# GD32F470.net
KiCad netlist of a schematic drawn in EAGLE
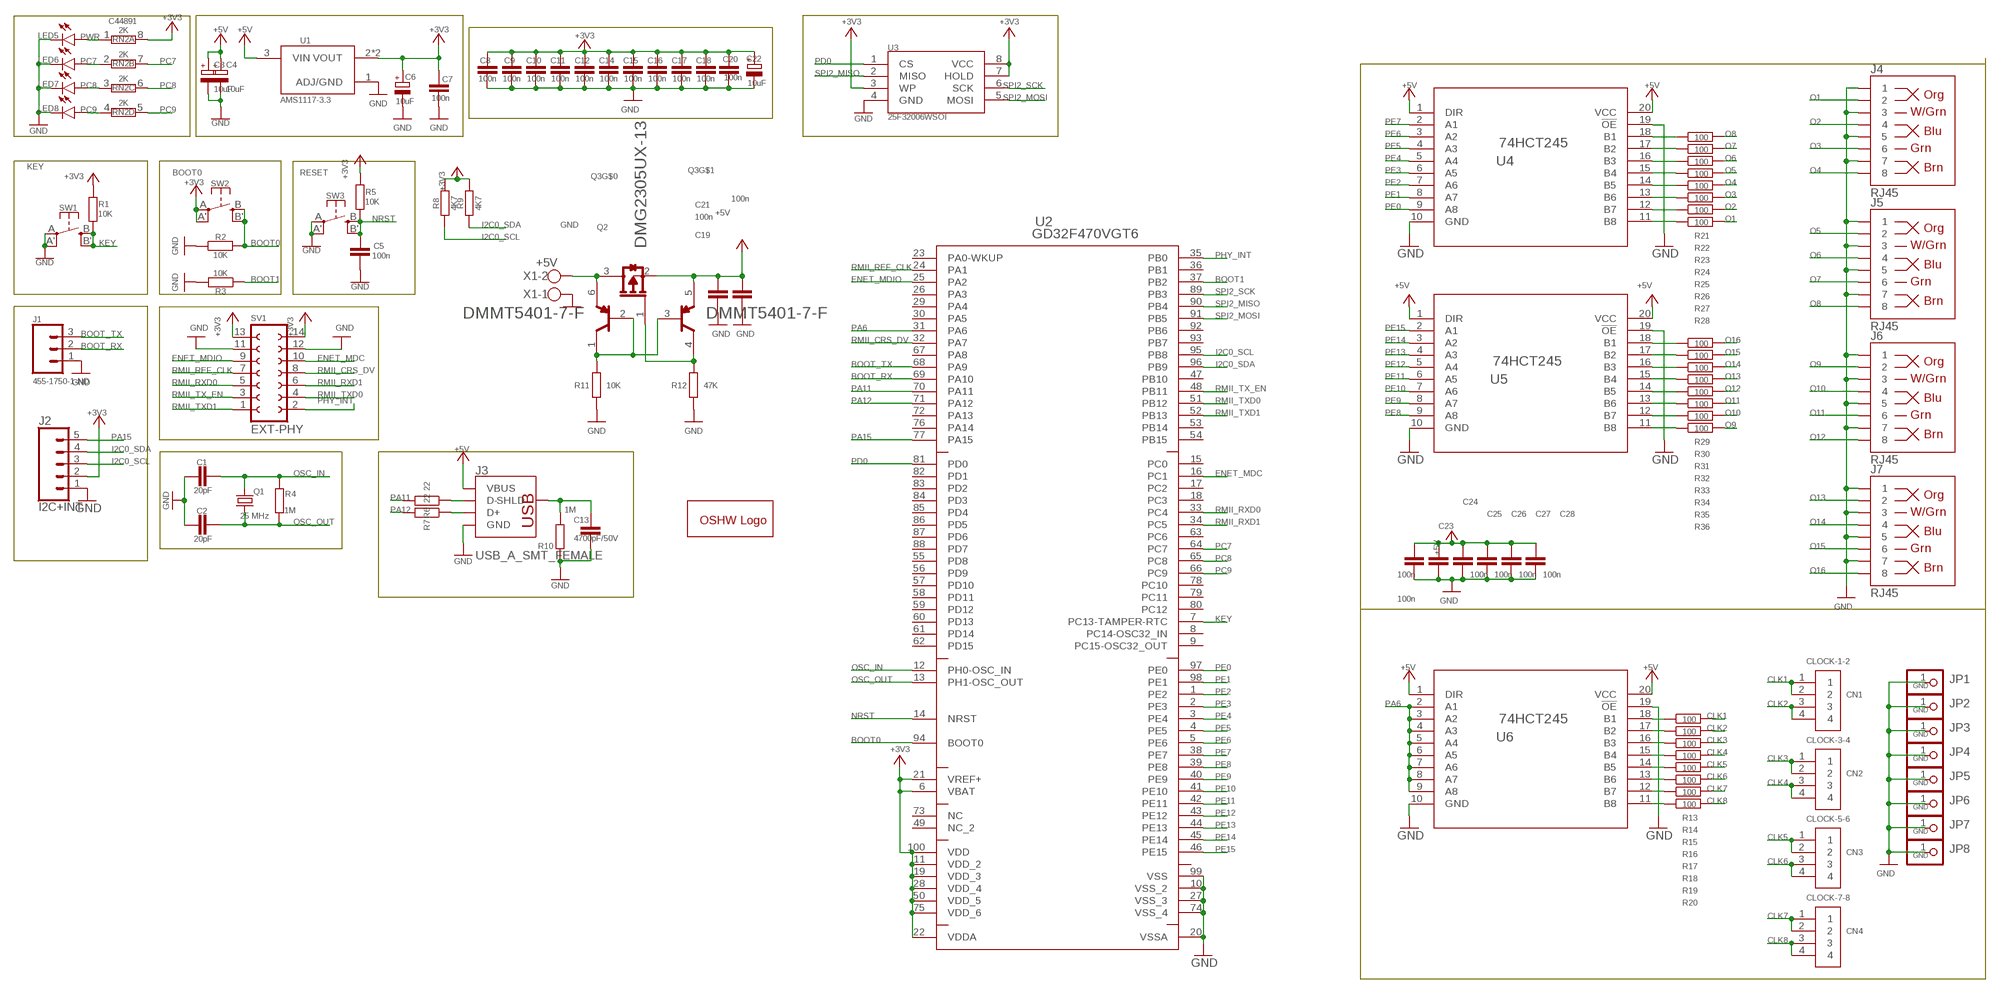
[diagram p0: schematic, sheet 1]

(export (version "E")
  (design (tool "Eeschema 10.0.6"))
  (components
    (comp (ref "C1")
      (value "20pF")
      (footprint "eagle-import:C0603")
      (libsource (lib "eagle-import") (part "C-EUC0603"))
    )
    (comp (ref "C2")
      (value "20pF")
      (footprint "eagle-import:C0603")
      (libsource (lib "eagle-import") (part "C-EUC0603"))
    )
    (comp (ref "C3")
      (value "10uF")
      (footprint "eagle-import:A_3216-18R")
      (libsource (lib "eagle-import") (part "CPOL-EUA/3216-18R"))
    )
    (comp (ref "C4")
      (value "10uF")
      (footprint "eagle-import:A_3216-18R")
      (libsource (lib "eagle-import") (part "CPOL-EUA/3216-18R"))
    )
    (comp (ref "C5")
      (value "100n")
      (footprint "eagle-import:C0603")
      (libsource (lib "eagle-import") (part "C-EUC0603"))
    )
    (comp (ref "C6")
      (value "10uF")
      (footprint "eagle-import:A_3216-18R")
      (libsource (lib "eagle-import") (part "CPOL-EUA/3216-18R"))
    )
    (comp (ref "C7")
      (value "100n")
      (footprint "eagle-import:C0603")
      (libsource (lib "eagle-import") (part "C-EUC0603"))
    )
    (comp (ref "C8")
      (value "100n")
      (footprint "eagle-import:C0603")
      (libsource (lib "eagle-import") (part "C-EUC0603"))
    )
    (comp (ref "C9")
      (value "100n")
      (footprint "eagle-import:C0603")
      (libsource (lib "eagle-import") (part "C-EUC0603"))
    )
    (comp (ref "C10")
      (value "100n")
      (footprint "eagle-import:C0603")
      (libsource (lib "eagle-import") (part "C-EUC0603"))
    )
    (comp (ref "C11")
      (value "100n")
      (footprint "eagle-import:C0603")
      (libsource (lib "eagle-import") (part "C-EUC0603"))
    )
    (comp (ref "C12")
      (value "100n")
      (footprint "eagle-import:C0603")
      (libsource (lib "eagle-import") (part "C-EUC0603"))
    )
    (comp (ref "C13")
      (value "4700pF/50V")
      (footprint "eagle-import:C0603")
      (libsource (lib "eagle-import") (part "C-EUC0603"))
    )
    (comp (ref "C14")
      (value "100n")
      (footprint "eagle-import:C0603")
      (libsource (lib "eagle-import") (part "C-EUC0603"))
    )
    (comp (ref "C15")
      (value "100n")
      (footprint "eagle-import:C0603")
      (libsource (lib "eagle-import") (part "C-EUC0603"))
    )
    (comp (ref "C16")
      (value "100n")
      (footprint "eagle-import:C0603")
      (libsource (lib "eagle-import") (part "C-EUC0603"))
    )
    (comp (ref "C17")
      (value "100n")
      (footprint "eagle-import:C0603")
      (libsource (lib "eagle-import") (part "C-EUC0603"))
    )
    (comp (ref "C18")
      (value "100n")
      (footprint "eagle-import:C0603")
      (libsource (lib "eagle-import") (part "C-EUC0603"))
    )
    (comp (ref "C19")
      (value "100n")
      (footprint "eagle-import:C0603")
      (libsource (lib "eagle-import") (part "C-EUC0603"))
    )
    (comp (ref "C20")
      (value "100n")
      (footprint "eagle-import:C0603")
      (libsource (lib "eagle-import") (part "C-EUC0603"))
    )
    (comp (ref "C21")
      (value "100n")
      (footprint "eagle-import:C0603")
      (libsource (lib "eagle-import") (part "C-EUC0603"))
    )
    (comp (ref "C22")
      (value "10uF")
      (footprint "eagle-import:A_3216-18R")
      (libsource (lib "eagle-import") (part "CPOL-EUA/3216-18R"))
    )
    (comp (ref "C23")
      (value "100n")
      (footprint "eagle-import:C0603")
      (libsource (lib "eagle-import") (part "C-EUC0603"))
    )
    (comp (ref "C24")
      (value "100n")
      (footprint "eagle-import:C0603")
      (libsource (lib "eagle-import") (part "C-EUC0603"))
    )
    (comp (ref "C25")
      (value "100n")
      (footprint "eagle-import:C0603")
      (libsource (lib "eagle-import") (part "C-EUC0603"))
    )
    (comp (ref "C26")
      (value "100n")
      (footprint "eagle-import:C0603")
      (libsource (lib "eagle-import") (part "C-EUC0603"))
    )
    (comp (ref "C27")
      (value "100n")
      (footprint "eagle-import:C0603")
      (libsource (lib "eagle-import") (part "C-EUC0603"))
    )
    (comp (ref "C28")
      (value "100n")
      (footprint "eagle-import:C0603")
      (libsource (lib "eagle-import") (part "C-EUC0603"))
    )
    (comp (ref "CN1")
      (value "CLOCK-1-2")
      (footprint "eagle-import:1X04-CLEANBIG")
      (libsource (lib "eagle-import") (part "1X4-CLEANBIG"))
    )
    (comp (ref "CN2")
      (value "CLOCK-3-4")
      (footprint "eagle-import:1X04-CLEANBIG")
      (libsource (lib "eagle-import") (part "1X4-CLEANBIG"))
    )
    (comp (ref "CN3")
      (value "CLOCK-5-6")
      (footprint "eagle-import:1X04-CLEANBIG")
      (libsource (lib "eagle-import") (part "1X4-CLEANBIG"))
    )
    (comp (ref "CN4")
      (value "CLOCK-7-8")
      (footprint "eagle-import:1X04-CLEANBIG")
      (libsource (lib "eagle-import") (part "1X4-CLEANBIG"))
    )
    (comp (ref "GOLD_ORB_SM1")
      (value "OSHWLOGOLOGO5MM")
      (footprint "eagle-import:OSHW_5MM")
      (libsource (lib "eagle-import") (part "OSHWLOGOLOGO5MM"))
    )
    (comp (ref "J1")
      (value "455-1750-1-ND")
      (footprint "eagle-import:1X03")
      (libsource (lib "eagle-import") (part "CONN_03"))
    )
    (comp (ref "J2")
      (value "I2C+INT")
      (footprint "eagle-import:1X05")
      (libsource (lib "eagle-import") (part "CONN_05PTH"))
    )
    (comp (ref "J3")
      (value "USB_A_SMT_FEMALE")
      (footprint "eagle-import:USB-A")
      (libsource (lib "eagle-import") (part "USB_A_SMT_FEMALE"))
    )
    (comp (ref "J4")
      (value "RJ45")
      (footprint "eagle-import:RJ45-8")
      (libsource (lib "eagle-import") (part "RJ45-8"))
    )
    (comp (ref "J5")
      (value "RJ45")
      (footprint "eagle-import:RJ45-8")
      (libsource (lib "eagle-import") (part "RJ45-8"))
    )
    (comp (ref "J6")
      (value "RJ45")
      (footprint "eagle-import:RJ45-8")
      (libsource (lib "eagle-import") (part "RJ45-8"))
    )
    (comp (ref "J7")
      (value "RJ45")
      (footprint "eagle-import:RJ45-8")
      (libsource (lib "eagle-import") (part "RJ45-8"))
    )
    (comp (ref "JP1")
      (value "GND")
      (footprint "eagle-import:1X01-CLEANBIG")
      (libsource (lib "eagle-import") (part "PINHD-1X1CB"))
    )
    (comp (ref "JP2")
      (value "GND")
      (footprint "eagle-import:1X01-CLEANBIG")
      (libsource (lib "eagle-import") (part "PINHD-1X1CB"))
    )
    (comp (ref "JP3")
      (value "GND")
      (footprint "eagle-import:1X01-CLEANBIG")
      (libsource (lib "eagle-import") (part "PINHD-1X1CB"))
    )
    (comp (ref "JP4")
      (value "GND")
      (footprint "eagle-import:1X01-CLEANBIG")
      (libsource (lib "eagle-import") (part "PINHD-1X1CB"))
    )
    (comp (ref "JP5")
      (value "GND")
      (footprint "eagle-import:1X01-CLEANBIG")
      (libsource (lib "eagle-import") (part "PINHD-1X1CB"))
    )
    (comp (ref "JP6")
      (value "GND")
      (footprint "eagle-import:1X01-CLEANBIG")
      (libsource (lib "eagle-import") (part "PINHD-1X1CB"))
    )
    (comp (ref "JP7")
      (value "GND")
      (footprint "eagle-import:1X01-CLEANBIG")
      (libsource (lib "eagle-import") (part "PINHD-1X1CB"))
    )
    (comp (ref "JP8")
      (value "GND")
      (footprint "eagle-import:1X01-CLEANBIG")
      (libsource (lib "eagle-import") (part "PINHD-1X1CB"))
    )
    (comp (ref "LED5")
      (value "PWR")
      (footprint "eagle-import:CHIP-LED0603")
      (libsource (lib "eagle-import") (part "LEDCHIP-LED0603"))
    )
    (comp (ref "LED6")
      (value "PC7")
      (footprint "eagle-import:CHIP-LED0603")
      (libsource (lib "eagle-import") (part "LEDCHIP-LED0603"))
    )
    (comp (ref "LED7")
      (value "PC8")
      (footprint "eagle-import:CHIP-LED0603")
      (libsource (lib "eagle-import") (part "LEDCHIP-LED0603"))
    )
    (comp (ref "LED8")
      (value "PC9")
      (footprint "eagle-import:CHIP-LED0603")
      (libsource (lib "eagle-import") (part "LEDCHIP-LED0603"))
    )
    (comp (ref "Q1")
      (value "25 MHz")
      (footprint "eagle-import:CSM-7X-DU")
      (libsource (lib "eagle-import") (part "CSM-7X-DU"))
    )
    (comp (ref "Q2")
      (value "DMG2305UX")
      (footprint "eagle-import:DIODES_INC._DMG2305UX-13_0")
      (fields
        (field (name "DIGIKEY_PART_NUMBER") "DMG2305UX-13DICT-ND")
        (field (name "MF") "Diodes Inc.")
        (field (name "MOUSER_PART_NUMBER") "621-DMG2305UX-13")
      )
      (libsource (lib "eagle-import") (part "DIODES_INC._DMG2305UX-13DIODES_INC._DMG2305UX-13_0_0"))
    )
    (comp (ref "Q3")
      (value "DMMT5401")
      (footprint "eagle-import:DIODES_DMMT5401-7-F_0")
      (fields
        (field (name "DIGIKEY_PART_NUMBER") "DMMT5401-FDICT-ND")
        (field (name "MF") "Diodes")
        (field (name "MOUSER_PART_NUMBER") "621-DMMT5401-7-F")
      )
      (libsource (lib "eagle-import") (part "DIODES_DMMT5401-7-FDIODES_DMMT5401-7-F_0_0"))
    )
    (comp (ref "R1")
      (value "10K")
      (footprint "eagle-import:R0603")
      (libsource (lib "eagle-import") (part "rcl_334_R-EU_R0603"))
    )
    (comp (ref "R2")
      (value "10K")
      (footprint "eagle-import:R0603")
      (libsource (lib "eagle-import") (part "rcl_334_R-EU_R0603"))
    )
    (comp (ref "R3")
      (value "10K")
      (footprint "eagle-import:R0603")
      (libsource (lib "eagle-import") (part "rcl_334_R-EU_R0603"))
    )
    (comp (ref "R4")
      (value "1M")
      (footprint "eagle-import:R0603")
      (libsource (lib "eagle-import") (part "rcl_334_R-EU_R0603"))
    )
    (comp (ref "R5")
      (value "10K")
      (footprint "eagle-import:R0603")
      (libsource (lib "eagle-import") (part "rcl_334_R-EU_R0603"))
    )
    (comp (ref "R6")
      (value "22")
      (footprint "eagle-import:R0402")
      (libsource (lib "eagle-import") (part "rcl_334_R-EU_R0402"))
    )
    (comp (ref "R7")
      (value "22")
      (footprint "eagle-import:R0402")
      (libsource (lib "eagle-import") (part "rcl_334_R-EU_R0402"))
    )
    (comp (ref "R8")
      (value "4K7")
      (footprint "eagle-import:R0402")
      (libsource (lib "eagle-import") (part "rcl_334_R-EU_R0402"))
    )
    (comp (ref "R9")
      (value "4K7")
      (footprint "eagle-import:R0402")
      (libsource (lib "eagle-import") (part "rcl_334_R-EU_R0402"))
    )
    (comp (ref "R10")
      (value "1M")
      (footprint "eagle-import:R0603")
      (libsource (lib "eagle-import") (part "R-EU_R0603"))
    )
    (comp (ref "R11")
      (value "10K")
      (footprint "eagle-import:R0402")
      (libsource (lib "eagle-import") (part "rcl_334_R-EU_R0402"))
    )
    (comp (ref "R12")
      (value "47K")
      (footprint "eagle-import:R0402")
      (libsource (lib "eagle-import") (part "rcl_334_R-EU_R0402"))
    )
    (comp (ref "R13")
      (value "100")
      (footprint "eagle-import:R0402")
      (libsource (lib "eagle-import") (part "rcl_334_R-EU_R0402"))
    )
    (comp (ref "R14")
      (value "100")
      (footprint "eagle-import:R0402")
      (libsource (lib "eagle-import") (part "rcl_334_R-EU_R0402"))
    )
    (comp (ref "R15")
      (value "100")
      (footprint "eagle-import:R0402")
      (libsource (lib "eagle-import") (part "rcl_334_R-EU_R0402"))
    )
    (comp (ref "R16")
      (value "100")
      (footprint "eagle-import:R0402")
      (libsource (lib "eagle-import") (part "rcl_334_R-EU_R0402"))
    )
    (comp (ref "R17")
      (value "100")
      (footprint "eagle-import:R0402")
      (libsource (lib "eagle-import") (part "rcl_334_R-EU_R0402"))
    )
    (comp (ref "R18")
      (value "100")
      (footprint "eagle-import:R0402")
      (libsource (lib "eagle-import") (part "rcl_334_R-EU_R0402"))
    )
    (comp (ref "R19")
      (value "100")
      (footprint "eagle-import:R0402")
      (libsource (lib "eagle-import") (part "rcl_334_R-EU_R0402"))
    )
    (comp (ref "R20")
      (value "100")
      (footprint "eagle-import:R0402")
      (libsource (lib "eagle-import") (part "rcl_334_R-EU_R0402"))
    )
    (comp (ref "R21")
      (value "100")
      (footprint "eagle-import:R0402")
      (libsource (lib "eagle-import") (part "rcl_334_R-EU_R0402"))
    )
    (comp (ref "R22")
      (value "100")
      (footprint "eagle-import:R0402")
      (libsource (lib "eagle-import") (part "rcl_334_R-EU_R0402"))
    )
    (comp (ref "R23")
      (value "100")
      (footprint "eagle-import:R0402")
      (libsource (lib "eagle-import") (part "rcl_334_R-EU_R0402"))
    )
    (comp (ref "R24")
      (value "100")
      (footprint "eagle-import:R0402")
      (libsource (lib "eagle-import") (part "rcl_334_R-EU_R0402"))
    )
    (comp (ref "R25")
      (value "100")
      (footprint "eagle-import:R0402")
      (libsource (lib "eagle-import") (part "rcl_334_R-EU_R0402"))
    )
    (comp (ref "R26")
      (value "100")
      (footprint "eagle-import:R0402")
      (libsource (lib "eagle-import") (part "rcl_334_R-EU_R0402"))
    )
    (comp (ref "R27")
      (value "100")
      (footprint "eagle-import:R0402")
      (libsource (lib "eagle-import") (part "rcl_334_R-EU_R0402"))
    )
    (comp (ref "R28")
      (value "100")
      (footprint "eagle-import:R0402")
      (libsource (lib "eagle-import") (part "rcl_334_R-EU_R0402"))
    )
    (comp (ref "R29")
      (value "100")
      (footprint "eagle-import:R0402")
      (libsource (lib "eagle-import") (part "rcl_334_R-EU_R0402"))
    )
    (comp (ref "R30")
      (value "100")
      (footprint "eagle-import:R0402")
      (libsource (lib "eagle-import") (part "rcl_334_R-EU_R0402"))
    )
    (comp (ref "R31")
      (value "100")
      (footprint "eagle-import:R0402")
      (libsource (lib "eagle-import") (part "rcl_334_R-EU_R0402"))
    )
    (comp (ref "R32")
      (value "100")
      (footprint "eagle-import:R0402")
      (libsource (lib "eagle-import") (part "rcl_334_R-EU_R0402"))
    )
    (comp (ref "R33")
      (value "100")
      (footprint "eagle-import:R0402")
      (libsource (lib "eagle-import") (part "rcl_334_R-EU_R0402"))
    )
    (comp (ref "R34")
      (value "100")
      (footprint "eagle-import:R0402")
      (libsource (lib "eagle-import") (part "rcl_334_R-EU_R0402"))
    )
    (comp (ref "R35")
      (value "100")
      (footprint "eagle-import:R0402")
      (libsource (lib "eagle-import") (part "rcl_334_R-EU_R0402"))
    )
    (comp (ref "R36")
      (value "100")
      (footprint "eagle-import:R0402")
      (libsource (lib "eagle-import") (part "rcl_334_R-EU_R0402"))
    )
    (comp (ref "RN2")
      (value "2K")
      (footprint "eagle-import:4X0402ARV341")
      (fields (field (name "JLCPCB") "C44891"))
      (libsource (lib "eagle-import") (part "4R-N0402ARV341"))
    )
    (comp (ref "SV1")
      (value "EXT-PHY")
      (footprint "eagle-import:FE07-2W")
      (libsource (lib "eagle-import") (part "FE07-2W"))
    )
    (comp (ref "SW1")
      (value "KEY")
      (footprint "eagle-import:EVQ-Q2")
      (libsource (lib "eagle-import") (part "SPST_TACT-EVQQ2"))
    )
    (comp (ref "SW2")
      (value "BOOT0")
      (footprint "eagle-import:EVQ-Q2")
      (libsource (lib "eagle-import") (part "SPST_TACT-EVQQ2"))
    )
    (comp (ref "SW3")
      (value "RESET")
      (footprint "eagle-import:EVQ-Q2")
      (libsource (lib "eagle-import") (part "SPST_TACT-EVQQ2"))
    )
    (comp (ref "U1")
      (value "AMS1117-3.3")
      (footprint "eagle-import:SOT229P700X180-4N")
      (fields (field (name "MF") "Advanced Monolithic Systems"))
      (libsource (lib "eagle-import") (part "AMS1117-3.3"))
    )
    (comp (ref "U2")
      (value "GD32F470VGT6")
      (footprint "eagle-import:LQFP100")
      (fields
        (field (name "MANUFACTURER_PART_NUMBER") "GD32F450VET6")
        (field (name "COPYRIGHT") "Copyright (C) 2022 Ultra Librarian. All rights reserved.")
      )
      (libsource (lib "eagle-import") (part "GD32F450VET6"))
    )
    (comp (ref "U3")
      (value "25F32006WSOI")
      (footprint "eagle-import:SO08-EIAJ")
      (libsource (lib "eagle-import") (part "SPI_FLASH-X25XXSMD1"))
    )
    (comp (ref "U4")
      (value "74HCT245")
      (footprint "eagle-import:PW20")
      (fields
        (field (name "GENERIC_PART_NUMBER") "SN74HCT245")
        (field (name "MANUFACTURER") "Texas Instruments")
        (field (name "MANUFACTURER_PART_NUMBER") "SN74HCT245PWR")
      )
      (libsource (lib "eagle-import") (part "SN74HCT245PWR"))
    )
    (comp (ref "U5")
      (value "74HCT245")
      (footprint "eagle-import:PW20")
      (fields
        (field (name "GENERIC_PART_NUMBER") "SN74HCT245")
        (field (name "MANUFACTURER") "Texas Instruments")
        (field (name "MANUFACTURER_PART_NUMBER") "SN74HCT245PWR")
      )
      (libsource (lib "eagle-import") (part "SN74HCT245PWR"))
    )
    (comp (ref "U6")
      (value "74HCT245")
      (footprint "eagle-import:PW20")
      (fields
        (field (name "GENERIC_PART_NUMBER") "SN74HCT245")
        (field (name "MANUFACTURER") "Texas Instruments")
        (field (name "MANUFACTURER_PART_NUMBER") "SN74HCT245PWR")
      )
      (libsource (lib "eagle-import") (part "SN74HCT245PWR"))
    )
    (comp (ref "X1")
      (value "+5V")
      (footprint "eagle-import:W237-102")
      (fields (field (name "MPN") "237-102"))
      (libsource (lib "eagle-import") (part "W237-102"))
    )
  )
  (nets
    (net (code "1") (name "+3V3") (class "Default")
      (node (ref "C10") (pin "1") (pinfunction "1_1") (pintype "passive"))
      (node (ref "C11") (pin "1") (pinfunction "1_1") (pintype "passive"))
      (node (ref "C12") (pin "1") (pinfunction "1_1") (pintype "passive"))
      (node (ref "C14") (pin "1") (pinfunction "1_1") (pintype "passive"))
      (node (ref "C15") (pin "1") (pinfunction "1_1") (pintype "passive"))
      (node (ref "C16") (pin "1") (pinfunction "1_1") (pintype "passive"))
      (node (ref "C17") (pin "1") (pinfunction "1_1") (pintype "passive"))
      (node (ref "C18") (pin "1") (pinfunction "1_1") (pintype "passive"))
      (node (ref "C20") (pin "1") (pinfunction "1_1") (pintype "passive"))
      (node (ref "C22") (pin "+") (pinfunction "+_+") (pintype "passive"))
      (node (ref "C6") (pin "+") (pinfunction "+_+") (pintype "passive"))
      (node (ref "C7") (pin "1") (pinfunction "1_1") (pintype "passive"))
      (node (ref "C8") (pin "1") (pinfunction "1_1") (pintype "passive"))
      (node (ref "C9") (pin "1") (pinfunction "1_1") (pintype "passive"))
      (node (ref "J2") (pin "2") (pinfunction "2_2") (pintype "passive"))
      (node (ref "R1") (pin "2") (pinfunction "2_2") (pintype "passive"))
      (node (ref "R5") (pin "2") (pinfunction "2_2") (pintype "passive"))
      (node (ref "R8") (pin "2") (pinfunction "2_2") (pintype "passive"))
      (node (ref "R9") (pin "2") (pinfunction "2_2") (pintype "passive"))
      (node (ref "RN2") (pin "8") (pinfunction "2_8") (pintype "passive"))
      (node (ref "SV1") (pin "13") (pinfunction "13_13") (pintype "passive"))
      (node (ref "SV1") (pin "14") (pinfunction "14_14") (pintype "passive"))
      (node (ref "SW2") (pin "A") (pinfunction "P_A") (pintype "passive"))
      (node (ref "SW2") (pin "A'") (pinfunction "P1_A'") (pintype "passive"))
      (node (ref "U1") (pin "2") (pinfunction "VOUT_2") (pintype "output"))
      (node (ref "U1") (pin "4") (pinfunction "VOUT_4") (pintype "output"))
      (node (ref "U2") (pin "100") (pinfunction "VDD_100") (pintype "power_in"))
      (node (ref "U2") (pin "11") (pinfunction "VDD_2_11") (pintype "power_in"))
      (node (ref "U2") (pin "19") (pinfunction "VDD_3_19") (pintype "power_in"))
      (node (ref "U2") (pin "21") (pinfunction "VREF+_21") (pintype "power_in"))
      (node (ref "U2") (pin "22") (pinfunction "VDDA_22") (pintype "power_in"))
      (node (ref "U2") (pin "28") (pinfunction "VDD_4_28") (pintype "power_in"))
      (node (ref "U2") (pin "50") (pinfunction "VDD_5_50") (pintype "power_in"))
      (node (ref "U2") (pin "6") (pinfunction "VBAT_6") (pintype "power_in"))
      (node (ref "U2") (pin "75") (pinfunction "VDD_6_75") (pintype "power_in"))
      (node (ref "U3") (pin "3") (pinfunction "WP_3") (pintype "bidirectional"))
      (node (ref "U3") (pin "7") (pinfunction "HOLD_7") (pintype "bidirectional"))
      (node (ref "U3") (pin "8") (pinfunction "VCC_8") (pintype "power_in"))
    )
    (net (code "2") (name "+5V") (class "Default")
      (node (ref "C19") (pin "1") (pinfunction "1_1") (pintype "passive"))
      (node (ref "C21") (pin "1") (pinfunction "1_1") (pintype "passive"))
      (node (ref "C23") (pin "1") (pinfunction "1_1") (pintype "passive"))
      (node (ref "C24") (pin "1") (pinfunction "1_1") (pintype "passive"))
      (node (ref "C25") (pin "1") (pinfunction "1_1") (pintype "passive"))
      (node (ref "C26") (pin "1") (pinfunction "1_1") (pintype "passive"))
      (node (ref "C27") (pin "1") (pinfunction "1_1") (pintype "passive"))
      (node (ref "C28") (pin "1") (pinfunction "1_1") (pintype "passive"))
      (node (ref "C3") (pin "+") (pinfunction "+_+") (pintype "passive"))
      (node (ref "C4") (pin "+") (pinfunction "+_+") (pintype "passive"))
      (node (ref "J3") (pin "VBUS") (pinfunction "VBUS_VBUS") (pintype "power_in"))
      (node (ref "Q2") (pin "2") (pinfunction "S_2") (pintype "passive"))
      (node (ref "Q3") (pin "5") (pinfunction "E2_5") (pintype "passive"))
      (node (ref "U1") (pin "3") (pinfunction "VIN_3") (pintype "input"))
      (node (ref "U4") (pin "1") (pinfunction "DIR_1") (pintype "input"))
      (node (ref "U4") (pin "20") (pinfunction "VCC_20") (pintype "power_in"))
      (node (ref "U5") (pin "1") (pinfunction "DIR_1") (pintype "input"))
      (node (ref "U5") (pin "20") (pinfunction "VCC_20") (pintype "power_in"))
      (node (ref "U6") (pin "1") (pinfunction "DIR_1") (pintype "input"))
      (node (ref "U6") (pin "20") (pinfunction "VCC_20") (pintype "power_in"))
    )
    (net (code "3") (name "/BOOT0") (class "Default")
      (node (ref "R2") (pin "2") (pinfunction "2_2") (pintype "passive"))
      (node (ref "SW2") (pin "B") (pinfunction "S_B") (pintype "passive"))
      (node (ref "SW2") (pin "B'") (pinfunction "S1_B'") (pintype "passive"))
      (node (ref "U2") (pin "94") (pinfunction "BOOT0_94") (pintype "input"))
    )
    (net (code "4") (name "/BOOT1") (class "Default")
      (node (ref "R3") (pin "1") (pinfunction "1_1") (pintype "passive"))
      (node (ref "U2") (pin "37") (pinfunction "PB2_37") (pintype "bidirectional"))
    )
    (net (code "5") (name "/BOOT_RX") (class "Default")
      (node (ref "J1") (pin "2") (pinfunction "2_2") (pintype "passive"))
      (node (ref "U2") (pin "69") (pinfunction "PA10_69") (pintype "bidirectional"))
    )
    (net (code "6") (name "/BOOT_TX") (class "Default")
      (node (ref "J1") (pin "3") (pinfunction "3_3") (pintype "passive"))
      (node (ref "U2") (pin "68") (pinfunction "PA9_68") (pintype "bidirectional"))
    )
    (net (code "7") (name "/CLK1") (class "Default")
      (node (ref "CN1") (pin "1") (pinfunction "1_1") (pintype "bidirectional"))
      (node (ref "CN1") (pin "2") (pinfunction "2_2") (pintype "bidirectional"))
      (node (ref "R13") (pin "2") (pinfunction "2_2") (pintype "passive"))
    )
    (net (code "8") (name "/CLK2") (class "Default")
      (node (ref "CN1") (pin "3") (pinfunction "3_3") (pintype "bidirectional"))
      (node (ref "CN1") (pin "4") (pinfunction "4_4") (pintype "bidirectional"))
      (node (ref "R14") (pin "2") (pinfunction "2_2") (pintype "passive"))
    )
    (net (code "9") (name "/CLK3") (class "Default")
      (node (ref "CN2") (pin "1") (pinfunction "1_1") (pintype "bidirectional"))
      (node (ref "CN2") (pin "2") (pinfunction "2_2") (pintype "bidirectional"))
      (node (ref "R15") (pin "2") (pinfunction "2_2") (pintype "passive"))
    )
    (net (code "10") (name "/CLK4") (class "Default")
      (node (ref "CN2") (pin "3") (pinfunction "3_3") (pintype "bidirectional"))
      (node (ref "CN2") (pin "4") (pinfunction "4_4") (pintype "bidirectional"))
      (node (ref "R16") (pin "2") (pinfunction "2_2") (pintype "passive"))
    )
    (net (code "11") (name "/CLK5") (class "Default")
      (node (ref "CN3") (pin "1") (pinfunction "1_1") (pintype "bidirectional"))
      (node (ref "CN3") (pin "2") (pinfunction "2_2") (pintype "bidirectional"))
      (node (ref "R17") (pin "2") (pinfunction "2_2") (pintype "passive"))
    )
    (net (code "12") (name "/CLK6") (class "Default")
      (node (ref "CN3") (pin "3") (pinfunction "3_3") (pintype "bidirectional"))
      (node (ref "CN3") (pin "4") (pinfunction "4_4") (pintype "bidirectional"))
      (node (ref "R18") (pin "2") (pinfunction "2_2") (pintype "passive"))
    )
    (net (code "13") (name "/CLK7") (class "Default")
      (node (ref "CN4") (pin "1") (pinfunction "1_1") (pintype "bidirectional"))
      (node (ref "CN4") (pin "2") (pinfunction "2_2") (pintype "bidirectional"))
      (node (ref "R19") (pin "2") (pinfunction "2_2") (pintype "passive"))
    )
    (net (code "14") (name "/CLK8") (class "Default")
      (node (ref "CN4") (pin "3") (pinfunction "3_3") (pintype "bidirectional"))
      (node (ref "CN4") (pin "4") (pinfunction "4_4") (pintype "bidirectional"))
      (node (ref "R20") (pin "2") (pinfunction "2_2") (pintype "passive"))
    )
    (net (code "15") (name "/ENET_MDC") (class "Default")
      (node (ref "SV1") (pin "10") (pinfunction "10_10") (pintype "passive"))
      (node (ref "U2") (pin "16") (pinfunction "PC1_16") (pintype "bidirectional"))
    )
    (net (code "16") (name "/ENET_MDIO") (class "Default")
      (node (ref "SV1") (pin "9") (pinfunction "9_9") (pintype "passive"))
      (node (ref "U2") (pin "25") (pinfunction "PA2_25") (pintype "bidirectional"))
    )
    (net (code "17") (name "/I2C0_SCL") (class "Default")
      (node (ref "J2") (pin "3") (pinfunction "3_3") (pintype "passive"))
      (node (ref "R8") (pin "1") (pinfunction "1_1") (pintype "passive"))
      (node (ref "U2") (pin "95") (pinfunction "PB8_95") (pintype "bidirectional"))
    )
    (net (code "18") (name "/I2C0_SDA") (class "Default")
      (node (ref "J2") (pin "4") (pinfunction "4_4") (pintype "passive"))
      (node (ref "R9") (pin "1") (pinfunction "1_1") (pintype "passive"))
      (node (ref "U2") (pin "96") (pinfunction "PB9_96") (pintype "bidirectional"))
    )
    (net (code "19") (name "/KEY") (class "Default")
      (node (ref "R1") (pin "1") (pinfunction "1_1") (pintype "passive"))
      (node (ref "SW1") (pin "B") (pinfunction "S_B") (pintype "passive"))
      (node (ref "SW1") (pin "B'") (pinfunction "S1_B'") (pintype "passive"))
      (node (ref "U2") (pin "7") (pinfunction "PC13-TAMPER-RTC_7") (pintype "bidirectional"))
    )
    (net (code "20") (name "/NRST") (class "Default")
      (node (ref "C5") (pin "1") (pinfunction "1_1") (pintype "passive"))
      (node (ref "R5") (pin "1") (pinfunction "1_1") (pintype "passive"))
      (node (ref "SW3") (pin "B") (pinfunction "S_B") (pintype "passive"))
      (node (ref "SW3") (pin "B'") (pinfunction "S1_B'") (pintype "passive"))
      (node (ref "U2") (pin "14") (pinfunction "NRST_14") (pintype "bidirectional"))
    )
    (net (code "21") (name "/O1") (class "Default")
      (node (ref "J4") (pin "2") (pinfunction "2_2") (pintype "bidirectional"))
      (node (ref "R28") (pin "2") (pinfunction "2_2") (pintype "passive"))
    )
    (net (code "22") (name "/O2") (class "Default")
      (node (ref "J4") (pin "4") (pinfunction "4_4") (pintype "bidirectional"))
      (node (ref "R27") (pin "2") (pinfunction "2_2") (pintype "passive"))
    )
    (net (code "23") (name "/O3") (class "Default")
      (node (ref "J4") (pin "6") (pinfunction "6_6") (pintype "bidirectional"))
      (node (ref "R26") (pin "2") (pinfunction "2_2") (pintype "passive"))
    )
    (net (code "24") (name "/O4") (class "Default")
      (node (ref "J4") (pin "8") (pinfunction "8_8") (pintype "bidirectional"))
      (node (ref "R25") (pin "2") (pinfunction "2_2") (pintype "passive"))
    )
    (net (code "25") (name "/O5") (class "Default")
      (node (ref "J5") (pin "2") (pinfunction "2_2") (pintype "bidirectional"))
      (node (ref "R24") (pin "2") (pinfunction "2_2") (pintype "passive"))
    )
    (net (code "26") (name "/O6") (class "Default")
      (node (ref "J5") (pin "4") (pinfunction "4_4") (pintype "bidirectional"))
      (node (ref "R23") (pin "2") (pinfunction "2_2") (pintype "passive"))
    )
    (net (code "27") (name "/O7") (class "Default")
      (node (ref "J5") (pin "6") (pinfunction "6_6") (pintype "bidirectional"))
      (node (ref "R22") (pin "2") (pinfunction "2_2") (pintype "passive"))
    )
    (net (code "28") (name "/O8") (class "Default")
      (node (ref "J5") (pin "8") (pinfunction "8_8") (pintype "bidirectional"))
      (node (ref "R21") (pin "2") (pinfunction "2_2") (pintype "passive"))
    )
    (net (code "29") (name "/O9") (class "Default")
      (node (ref "J6") (pin "2") (pinfunction "2_2") (pintype "bidirectional"))
      (node (ref "R36") (pin "2") (pinfunction "2_2") (pintype "passive"))
    )
    (net (code "30") (name "/O10") (class "Default")
      (node (ref "J6") (pin "4") (pinfunction "4_4") (pintype "bidirectional"))
      (node (ref "R35") (pin "2") (pinfunction "2_2") (pintype "passive"))
    )
    (net (code "31") (name "/O11") (class "Default")
      (node (ref "J6") (pin "6") (pinfunction "6_6") (pintype "bidirectional"))
      (node (ref "R34") (pin "2") (pinfunction "2_2") (pintype "passive"))
    )
    (net (code "32") (name "/O12") (class "Default")
      (node (ref "J6") (pin "8") (pinfunction "8_8") (pintype "bidirectional"))
      (node (ref "R33") (pin "2") (pinfunction "2_2") (pintype "passive"))
    )
    (net (code "33") (name "/O13") (class "Default")
      (node (ref "J7") (pin "2") (pinfunction "2_2") (pintype "bidirectional"))
      (node (ref "R32") (pin "2") (pinfunction "2_2") (pintype "passive"))
    )
    (net (code "34") (name "/O14") (class "Default")
      (node (ref "J7") (pin "4") (pinfunction "4_4") (pintype "bidirectional"))
      (node (ref "R31") (pin "2") (pinfunction "2_2") (pintype "passive"))
    )
    (net (code "35") (name "/O15") (class "Default")
      (node (ref "J7") (pin "6") (pinfunction "6_6") (pintype "bidirectional"))
      (node (ref "R30") (pin "2") (pinfunction "2_2") (pintype "passive"))
    )
    (net (code "36") (name "/O16") (class "Default")
      (node (ref "J7") (pin "8") (pinfunction "8_8") (pintype "bidirectional"))
      (node (ref "R29") (pin "2") (pinfunction "2_2") (pintype "passive"))
    )
    (net (code "37") (name "/OSC_IN") (class "Default")
      (node (ref "C1") (pin "2") (pinfunction "2_2") (pintype "passive"))
      (node (ref "Q1") (pin "2") (pinfunction "2_2") (pintype "passive"))
      (node (ref "R4") (pin "1") (pinfunction "1_1") (pintype "passive"))
      (node (ref "U2") (pin "12") (pinfunction "PH0-OSC_IN_12") (pintype "bidirectional"))
    )
    (net (code "38") (name "/OSC_OUT") (class "Default")
      (node (ref "C2") (pin "2") (pinfunction "2_2") (pintype "passive"))
      (node (ref "Q1") (pin "1") (pinfunction "1_1") (pintype "passive"))
      (node (ref "R4") (pin "2") (pinfunction "2_2") (pintype "passive"))
      (node (ref "U2") (pin "13") (pinfunction "PH1-OSC_OUT_13") (pintype "bidirectional"))
    )
    (net (code "39") (name "/PA6") (class "Default")
      (node (ref "U2") (pin "31") (pinfunction "PA6_31") (pintype "bidirectional"))
      (node (ref "U6") (pin "2") (pinfunction "A1_2") (pintype "bidirectional"))
      (node (ref "U6") (pin "3") (pinfunction "A2_3") (pintype "bidirectional"))
      (node (ref "U6") (pin "4") (pinfunction "A3_4") (pintype "bidirectional"))
      (node (ref "U6") (pin "5") (pinfunction "A4_5") (pintype "bidirectional"))
      (node (ref "U6") (pin "6") (pinfunction "A5_6") (pintype "bidirectional"))
      (node (ref "U6") (pin "7") (pinfunction "A6_7") (pintype "bidirectional"))
      (node (ref "U6") (pin "8") (pinfunction "A7_8") (pintype "bidirectional"))
      (node (ref "U6") (pin "9") (pinfunction "A8_9") (pintype "bidirectional"))
    )
    (net (code "40") (name "/PA11") (class "Default")
      (node (ref "R6") (pin "2") (pinfunction "2_2") (pintype "passive"))
      (node (ref "U2") (pin "70") (pinfunction "PA11_70") (pintype "bidirectional"))
    )
    (net (code "41") (name "/PA12") (class "Default")
      (node (ref "R7") (pin "2") (pinfunction "2_2") (pintype "passive"))
      (node (ref "U2") (pin "71") (pinfunction "PA12_71") (pintype "bidirectional"))
    )
    (net (code "42") (name "/PA15") (class "Default")
      (node (ref "J2") (pin "5") (pinfunction "5_5") (pintype "passive"))
      (node (ref "U2") (pin "77") (pinfunction "PA15_77") (pintype "bidirectional"))
    )
    (net (code "43") (name "/PC7") (class "Default")
      (node (ref "RN2") (pin "7") (pinfunction "2_7") (pintype "passive"))
      (node (ref "U2") (pin "64") (pinfunction "PC7_64") (pintype "bidirectional"))
    )
    (net (code "44") (name "/PC8") (class "Default")
      (node (ref "RN2") (pin "6") (pinfunction "2_6") (pintype "passive"))
      (node (ref "U2") (pin "65") (pinfunction "PC8_65") (pintype "bidirectional"))
    )
    (net (code "45") (name "/PC9") (class "Default")
      (node (ref "RN2") (pin "5") (pinfunction "2_5") (pintype "passive"))
      (node (ref "U2") (pin "66") (pinfunction "PC9_66") (pintype "bidirectional"))
    )
    (net (code "46") (name "/PD0") (class "Default")
      (node (ref "U2") (pin "81") (pinfunction "PD0_81") (pintype "bidirectional"))
      (node (ref "U3") (pin "1") (pinfunction "CS_1") (pintype "bidirectional"))
    )
    (net (code "47") (name "/PE0") (class "Default")
      (node (ref "U2") (pin "97") (pinfunction "PE0_97") (pintype "bidirectional"))
      (node (ref "U4") (pin "9") (pinfunction "A8_9") (pintype "bidirectional"))
    )
    (net (code "48") (name "/PE1") (class "Default")
      (node (ref "U2") (pin "98") (pinfunction "PE1_98") (pintype "bidirectional"))
      (node (ref "U4") (pin "8") (pinfunction "A7_8") (pintype "bidirectional"))
    )
    (net (code "49") (name "/PE2") (class "Default")
      (node (ref "U2") (pin "1") (pinfunction "PE2_1") (pintype "bidirectional"))
      (node (ref "U4") (pin "7") (pinfunction "A6_7") (pintype "bidirectional"))
    )
    (net (code "50") (name "/PE3") (class "Default")
      (node (ref "U2") (pin "2") (pinfunction "PE3_2") (pintype "bidirectional"))
      (node (ref "U4") (pin "6") (pinfunction "A5_6") (pintype "bidirectional"))
    )
    (net (code "51") (name "/PE4") (class "Default")
      (node (ref "U2") (pin "3") (pinfunction "PE4_3") (pintype "bidirectional"))
      (node (ref "U4") (pin "5") (pinfunction "A4_5") (pintype "bidirectional"))
    )
    (net (code "52") (name "/PE5") (class "Default")
      (node (ref "U2") (pin "4") (pinfunction "PE5_4") (pintype "bidirectional"))
      (node (ref "U4") (pin "4") (pinfunction "A3_4") (pintype "bidirectional"))
    )
    (net (code "53") (name "/PE6") (class "Default")
      (node (ref "U2") (pin "5") (pinfunction "PE6_5") (pintype "bidirectional"))
      (node (ref "U4") (pin "3") (pinfunction "A2_3") (pintype "bidirectional"))
    )
    (net (code "54") (name "/PE7") (class "Default")
      (node (ref "U2") (pin "38") (pinfunction "PE7_38") (pintype "bidirectional"))
      (node (ref "U4") (pin "2") (pinfunction "A1_2") (pintype "bidirectional"))
    )
    (net (code "55") (name "/PE8") (class "Default")
      (node (ref "U2") (pin "39") (pinfunction "PE8_39") (pintype "bidirectional"))
      (node (ref "U5") (pin "9") (pinfunction "A8_9") (pintype "bidirectional"))
    )
    (net (code "56") (name "/PE9") (class "Default")
      (node (ref "U2") (pin "40") (pinfunction "PE9_40") (pintype "bidirectional"))
      (node (ref "U5") (pin "8") (pinfunction "A7_8") (pintype "bidirectional"))
    )
    (net (code "57") (name "/PE10") (class "Default")
      (node (ref "U2") (pin "41") (pinfunction "PE10_41") (pintype "bidirectional"))
      (node (ref "U5") (pin "7") (pinfunction "A6_7") (pintype "bidirectional"))
    )
    (net (code "58") (name "/PE11") (class "Default")
      (node (ref "U2") (pin "42") (pinfunction "PE11_42") (pintype "bidirectional"))
      (node (ref "U5") (pin "6") (pinfunction "A5_6") (pintype "bidirectional"))
    )
    (net (code "59") (name "/PE12") (class "Default")
      (node (ref "U2") (pin "43") (pinfunction "PE12_43") (pintype "bidirectional"))
      (node (ref "U5") (pin "5") (pinfunction "A4_5") (pintype "bidirectional"))
    )
    (net (code "60") (name "/PE13") (class "Default")
      (node (ref "U2") (pin "44") (pinfunction "PE13_44") (pintype "bidirectional"))
      (node (ref "U5") (pin "4") (pinfunction "A3_4") (pintype "bidirectional"))
    )
    (net (code "61") (name "/PE14") (class "Default")
      (node (ref "U2") (pin "45") (pinfunction "PE14_45") (pintype "bidirectional"))
      (node (ref "U5") (pin "3") (pinfunction "A2_3") (pintype "bidirectional"))
    )
    (net (code "62") (name "/PE15") (class "Default")
      (node (ref "U2") (pin "46") (pinfunction "PE15_46") (pintype "bidirectional"))
      (node (ref "U5") (pin "2") (pinfunction "A1_2") (pintype "bidirectional"))
    )
    (net (code "63") (name "/PHY_INT") (class "Default")
      (node (ref "SV1") (pin "2") (pinfunction "2_2") (pintype "passive"))
      (node (ref "U2") (pin "35") (pinfunction "PB0_35") (pintype "bidirectional"))
    )
    (net (code "64") (name "/RMII_CRS_DV") (class "Default")
      (node (ref "SV1") (pin "8") (pinfunction "8_8") (pintype "passive"))
      (node (ref "U2") (pin "32") (pinfunction "PA7_32") (pintype "bidirectional"))
    )
    (net (code "65") (name "/RMII_REF_CLK") (class "Default")
      (node (ref "SV1") (pin "7") (pinfunction "7_7") (pintype "passive"))
      (node (ref "U2") (pin "24") (pinfunction "PA1_24") (pintype "bidirectional"))
    )
    (net (code "66") (name "/RMII_RXD0") (class "Default")
      (node (ref "SV1") (pin "5") (pinfunction "5_5") (pintype "passive"))
      (node (ref "U2") (pin "33") (pinfunction "PC4_33") (pintype "bidirectional"))
    )
    (net (code "67") (name "/RMII_RXD1") (class "Default")
      (node (ref "SV1") (pin "6") (pinfunction "6_6") (pintype "passive"))
      (node (ref "U2") (pin "34") (pinfunction "PC5_34") (pintype "bidirectional"))
    )
    (net (code "68") (name "/RMII_TXD0") (class "Default")
      (node (ref "SV1") (pin "4") (pinfunction "4_4") (pintype "passive"))
      (node (ref "U2") (pin "51") (pinfunction "PB12_51") (pintype "bidirectional"))
    )
    (net (code "69") (name "/RMII_TXD1") (class "Default")
      (node (ref "SV1") (pin "1") (pinfunction "1_1") (pintype "passive"))
      (node (ref "U2") (pin "52") (pinfunction "PB13_52") (pintype "bidirectional"))
    )
    (net (code "70") (name "/RMII_TX_EN") (class "Default")
      (node (ref "SV1") (pin "3") (pinfunction "3_3") (pintype "passive"))
      (node (ref "U2") (pin "48") (pinfunction "PB11_48") (pintype "bidirectional"))
    )
    (net (code "71") (name "/SPI2_MISO") (class "Default")
      (node (ref "U2") (pin "90") (pinfunction "PB4_90") (pintype "bidirectional"))
      (node (ref "U3") (pin "2") (pinfunction "MISO_2") (pintype "bidirectional"))
    )
    (net (code "72") (name "/SPI2_MOSI") (class "Default")
      (node (ref "U2") (pin "91") (pinfunction "PB5_91") (pintype "bidirectional"))
      (node (ref "U3") (pin "5") (pinfunction "MOSI_5") (pintype "bidirectional"))
    )
    (net (code "73") (name "/SPI2_SCK") (class "Default")
      (node (ref "U2") (pin "89") (pinfunction "PB3_89") (pintype "bidirectional"))
      (node (ref "U3") (pin "6") (pinfunction "SCK_6") (pintype "bidirectional"))
    )
    (net (code "74") (name "GND") (class "Default")
      (node (ref "C1") (pin "1") (pinfunction "1_1") (pintype "passive"))
      (node (ref "C10") (pin "2") (pinfunction "2_2") (pintype "passive"))
      (node (ref "C11") (pin "2") (pinfunction "2_2") (pintype "passive"))
      (node (ref "C12") (pin "2") (pinfunction "2_2") (pintype "passive"))
      (node (ref "C13") (pin "2") (pinfunction "2_2") (pintype "passive"))
      (node (ref "C14") (pin "2") (pinfunction "2_2") (pintype "passive"))
      (node (ref "C15") (pin "2") (pinfunction "2_2") (pintype "passive"))
      (node (ref "C16") (pin "2") (pinfunction "2_2") (pintype "passive"))
      (node (ref "C17") (pin "2") (pinfunction "2_2") (pintype "passive"))
      (node (ref "C18") (pin "2") (pinfunction "2_2") (pintype "passive"))
      (node (ref "C19") (pin "2") (pinfunction "2_2") (pintype "passive"))
      (node (ref "C2") (pin "1") (pinfunction "1_1") (pintype "passive"))
      (node (ref "C20") (pin "2") (pinfunction "2_2") (pintype "passive"))
      (node (ref "C21") (pin "2") (pinfunction "2_2") (pintype "passive"))
      (node (ref "C22") (pin "-") (pinfunction "-_-") (pintype "passive"))
      (node (ref "C23") (pin "2") (pinfunction "2_2") (pintype "passive"))
      (node (ref "C24") (pin "2") (pinfunction "2_2") (pintype "passive"))
      (node (ref "C25") (pin "2") (pinfunction "2_2") (pintype "passive"))
      (node (ref "C26") (pin "2") (pinfunction "2_2") (pintype "passive"))
      (node (ref "C27") (pin "2") (pinfunction "2_2") (pintype "passive"))
      (node (ref "C28") (pin "2") (pinfunction "2_2") (pintype "passive"))
      (node (ref "C3") (pin "-") (pinfunction "-_-") (pintype "passive"))
      (node (ref "C4") (pin "-") (pinfunction "-_-") (pintype "passive"))
      (node (ref "C5") (pin "2") (pinfunction "2_2") (pintype "passive"))
      (node (ref "C6") (pin "-") (pinfunction "-_-") (pintype "passive"))
      (node (ref "C7") (pin "2") (pinfunction "2_2") (pintype "passive"))
      (node (ref "C8") (pin "2") (pinfunction "2_2") (pintype "passive"))
      (node (ref "C9") (pin "2") (pinfunction "2_2") (pintype "passive"))
      (node (ref "J1") (pin "1") (pinfunction "1_1") (pintype "passive"))
      (node (ref "J2") (pin "1") (pinfunction "1_1") (pintype "passive"))
      (node (ref "J3") (pin "GND") (pinfunction "GND_GND") (pintype "power_in"))
      (node (ref "J4") (pin "1") (pinfunction "1_1") (pintype "bidirectional"))
      (node (ref "J4") (pin "3") (pinfunction "3_3") (pintype "bidirectional"))
      (node (ref "J4") (pin "5") (pinfunction "5_5") (pintype "bidirectional"))
      (node (ref "J4") (pin "7") (pinfunction "7_7") (pintype "bidirectional"))
      (node (ref "J5") (pin "1") (pinfunction "1_1") (pintype "bidirectional"))
      (node (ref "J5") (pin "3") (pinfunction "3_3") (pintype "bidirectional"))
      (node (ref "J5") (pin "5") (pinfunction "5_5") (pintype "bidirectional"))
      (node (ref "J5") (pin "7") (pinfunction "7_7") (pintype "bidirectional"))
      (node (ref "J6") (pin "1") (pinfunction "1_1") (pintype "bidirectional"))
      (node (ref "J6") (pin "3") (pinfunction "3_3") (pintype "bidirectional"))
      (node (ref "J6") (pin "5") (pinfunction "5_5") (pintype "bidirectional"))
      (node (ref "J6") (pin "7") (pinfunction "7_7") (pintype "bidirectional"))
      (node (ref "J7") (pin "1") (pinfunction "1_1") (pintype "bidirectional"))
      (node (ref "J7") (pin "3") (pinfunction "3_3") (pintype "bidirectional"))
      (node (ref "J7") (pin "5") (pinfunction "5_5") (pintype "bidirectional"))
      (node (ref "J7") (pin "7") (pinfunction "7_7") (pintype "bidirectional"))
      (node (ref "JP1") (pin "1") (pinfunction "1_1") (pintype "passive"))
      (node (ref "JP2") (pin "1") (pinfunction "1_1") (pintype "passive"))
      (node (ref "JP3") (pin "1") (pinfunction "1_1") (pintype "passive"))
      (node (ref "JP4") (pin "1") (pinfunction "1_1") (pintype "passive"))
      (node (ref "JP5") (pin "1") (pinfunction "1_1") (pintype "passive"))
      (node (ref "JP6") (pin "1") (pinfunction "1_1") (pintype "passive"))
      (node (ref "JP7") (pin "1") (pinfunction "1_1") (pintype "passive"))
      (node (ref "JP8") (pin "1") (pinfunction "1_1") (pintype "passive"))
      (node (ref "LED5") (pin "C") (pinfunction "C_C") (pintype "passive"))
      (node (ref "LED6") (pin "C") (pinfunction "C_C") (pintype "passive"))
      (node (ref "LED7") (pin "C") (pinfunction "C_C") (pintype "passive"))
      (node (ref "LED8") (pin "C") (pinfunction "C_C") (pintype "passive"))
      (node (ref "R10") (pin "1") (pinfunction "1_1") (pintype "passive"))
      (node (ref "R11") (pin "1") (pinfunction "1_1") (pintype "passive"))
      (node (ref "R12") (pin "1") (pinfunction "1_1") (pintype "passive"))
      (node (ref "R2") (pin "1") (pinfunction "1_1") (pintype "passive"))
      (node (ref "R3") (pin "2") (pinfunction "2_2") (pintype "passive"))
      (node (ref "SV1") (pin "11") (pinfunction "11_11") (pintype "passive"))
      (node (ref "SV1") (pin "12") (pinfunction "12_12") (pintype "passive"))
      (node (ref "SW1") (pin "A") (pinfunction "P_A") (pintype "passive"))
      (node (ref "SW1") (pin "A'") (pinfunction "P1_A'") (pintype "passive"))
      (node (ref "SW3") (pin "A") (pinfunction "P_A") (pintype "passive"))
      (node (ref "SW3") (pin "A'") (pinfunction "P1_A'") (pintype "passive"))
      (node (ref "U1") (pin "1") (pinfunction "ADJ/GND_1") (pintype "power_in"))
      (node (ref "U2") (pin "10") (pinfunction "VSS_2_10") (pintype "passive"))
      (node (ref "U2") (pin "20") (pinfunction "VSSA_20") (pintype "passive"))
      (node (ref "U2") (pin "27") (pinfunction "VSS_3_27") (pintype "passive"))
      (node (ref "U2") (pin "74") (pinfunction "VSS_4_74") (pintype "passive"))
      (node (ref "U2") (pin "99") (pinfunction "VSS_99") (pintype "passive"))
      (node (ref "U3") (pin "4") (pinfunction "GND_4") (pintype "power_in"))
      (node (ref "U4") (pin "10") (pinfunction "GND_10") (pintype "power_in"))
      (node (ref "U4") (pin "19") (pinfunction "~{OE}_19") (pintype "input"))
      (node (ref "U5") (pin "10") (pinfunction "GND_10") (pintype "power_in"))
      (node (ref "U5") (pin "19") (pinfunction "~{OE}_19") (pintype "input"))
      (node (ref "U6") (pin "10") (pinfunction "GND_10") (pintype "power_in"))
      (node (ref "U6") (pin "19") (pinfunction "~{OE}_19") (pintype "input"))
      (node (ref "X1") (pin "1") (pinfunction "KL_1") (pintype "passive"))
    )
    (net (code "75") (name "Net-(C13-Pad1)") (class "Default")
      (node (ref "C13") (pin "1") (pinfunction "1_1") (pintype "passive"))
      (node (ref "J3") (pin "SHLD1") (pinfunction "SHLD_SHLD1") (pintype "bidirectional"))
      (node (ref "J3") (pin "SHLD2") (pinfunction "SHLD_SHLD2") (pintype "bidirectional"))
      (node (ref "R10") (pin "2") (pinfunction "2_2") (pintype "passive"))
    )
    (net (code "76") (name "Net-(J3-PadD+)") (class "Default")
      (node (ref "J3") (pin "D+") (pinfunction "D+_D+") (pintype "bidirectional"))
      (node (ref "R7") (pin "1") (pinfunction "1_1") (pintype "passive"))
    )
    (net (code "77") (name "Net-(J3-PadD-)") (class "Default")
      (node (ref "J3") (pin "D-") (pinfunction "D-_D-") (pintype "bidirectional"))
      (node (ref "R6") (pin "1") (pinfunction "1_1") (pintype "passive"))
    )
    (net (code "78") (name "Net-(LED5-PadA)") (class "Default")
      (node (ref "LED5") (pin "A") (pinfunction "A_A") (pintype "passive"))
      (node (ref "RN2") (pin "1") (pinfunction "1_1") (pintype "passive"))
    )
    (net (code "79") (name "Net-(Q2-D)") (class "Default")
      (node (ref "Q2") (pin "3") (pinfunction "D_3") (pintype "passive"))
      (node (ref "Q3") (pin "6") (pinfunction "E1_6") (pintype "passive"))
      (node (ref "X1") (pin "2") (pinfunction "KL_2") (pintype "passive"))
    )
    (net (code "80") (name "Net-(Q2-G)") (class "Default")
      (node (ref "Q2") (pin "1") (pinfunction "G_1") (pintype "passive"))
      (node (ref "Q3") (pin "4") (pinfunction "C2_4") (pintype "passive"))
      (node (ref "R12") (pin "2") (pinfunction "2_2") (pintype "passive"))
    )
    (net (code "81") (name "Net-(Q3A-B1)") (class "Default")
      (node (ref "Q3") (pin "1") (pinfunction "C1_1") (pintype "passive"))
      (node (ref "Q3") (pin "2") (pinfunction "B1_2") (pintype "passive"))
      (node (ref "Q3") (pin "3") (pinfunction "B2_3") (pintype "passive"))
      (node (ref "R11") (pin "2") (pinfunction "2_2") (pintype "passive"))
    )
    (net (code "82") (name "Net-(RN2B-1)") (class "Default")
      (node (ref "LED6") (pin "A") (pinfunction "A_A") (pintype "passive"))
      (node (ref "RN2") (pin "2") (pinfunction "1_2") (pintype "passive"))
    )
    (net (code "83") (name "Net-(RN2C-1)") (class "Default")
      (node (ref "LED7") (pin "A") (pinfunction "A_A") (pintype "passive"))
      (node (ref "RN2") (pin "3") (pinfunction "1_3") (pintype "passive"))
    )
    (net (code "84") (name "Net-(RN2D-1)") (class "Default")
      (node (ref "LED8") (pin "A") (pinfunction "A_A") (pintype "passive"))
      (node (ref "RN2") (pin "4") (pinfunction "1_4") (pintype "passive"))
    )
    (net (code "85") (name "Net-(U4-B1)") (class "Default")
      (node (ref "R21") (pin "1") (pinfunction "1_1") (pintype "passive"))
      (node (ref "U4") (pin "18") (pinfunction "B1_18") (pintype "bidirectional"))
    )
    (net (code "86") (name "Net-(U4-B2)") (class "Default")
      (node (ref "R22") (pin "1") (pinfunction "1_1") (pintype "passive"))
      (node (ref "U4") (pin "17") (pinfunction "B2_17") (pintype "bidirectional"))
    )
    (net (code "87") (name "Net-(U4-B3)") (class "Default")
      (node (ref "R23") (pin "1") (pinfunction "1_1") (pintype "passive"))
      (node (ref "U4") (pin "16") (pinfunction "B3_16") (pintype "bidirectional"))
    )
    (net (code "88") (name "Net-(U4-B4)") (class "Default")
      (node (ref "R24") (pin "1") (pinfunction "1_1") (pintype "passive"))
      (node (ref "U4") (pin "15") (pinfunction "B4_15") (pintype "bidirectional"))
    )
    (net (code "89") (name "Net-(U4-B5)") (class "Default")
      (node (ref "R25") (pin "1") (pinfunction "1_1") (pintype "passive"))
      (node (ref "U4") (pin "14") (pinfunction "B5_14") (pintype "bidirectional"))
    )
    (net (code "90") (name "Net-(U4-B6)") (class "Default")
      (node (ref "R26") (pin "1") (pinfunction "1_1") (pintype "passive"))
      (node (ref "U4") (pin "13") (pinfunction "B6_13") (pintype "bidirectional"))
    )
    (net (code "91") (name "Net-(U4-B7)") (class "Default")
      (node (ref "R27") (pin "1") (pinfunction "1_1") (pintype "passive"))
      (node (ref "U4") (pin "12") (pinfunction "B7_12") (pintype "bidirectional"))
    )
    (net (code "92") (name "Net-(U4-B8)") (class "Default")
      (node (ref "R28") (pin "1") (pinfunction "1_1") (pintype "passive"))
      (node (ref "U4") (pin "11") (pinfunction "B8_11") (pintype "bidirectional"))
    )
    (net (code "93") (name "Net-(U5-B1)") (class "Default")
      (node (ref "R29") (pin "1") (pinfunction "1_1") (pintype "passive"))
      (node (ref "U5") (pin "18") (pinfunction "B1_18") (pintype "bidirectional"))
    )
    (net (code "94") (name "Net-(U5-B2)") (class "Default")
      (node (ref "R30") (pin "1") (pinfunction "1_1") (pintype "passive"))
      (node (ref "U5") (pin "17") (pinfunction "B2_17") (pintype "bidirectional"))
    )
    (net (code "95") (name "Net-(U5-B3)") (class "Default")
      (node (ref "R31") (pin "1") (pinfunction "1_1") (pintype "passive"))
      (node (ref "U5") (pin "16") (pinfunction "B3_16") (pintype "bidirectional"))
    )
    (net (code "96") (name "Net-(U5-B4)") (class "Default")
      (node (ref "R32") (pin "1") (pinfunction "1_1") (pintype "passive"))
      (node (ref "U5") (pin "15") (pinfunction "B4_15") (pintype "bidirectional"))
    )
    (net (code "97") (name "Net-(U5-B5)") (class "Default")
      (node (ref "R33") (pin "1") (pinfunction "1_1") (pintype "passive"))
      (node (ref "U5") (pin "14") (pinfunction "B5_14") (pintype "bidirectional"))
    )
    (net (code "98") (name "Net-(U5-B6)") (class "Default")
      (node (ref "R34") (pin "1") (pinfunction "1_1") (pintype "passive"))
      (node (ref "U5") (pin "13") (pinfunction "B6_13") (pintype "bidirectional"))
    )
    (net (code "99") (name "Net-(U5-B7)") (class "Default")
      (node (ref "R35") (pin "1") (pinfunction "1_1") (pintype "passive"))
      (node (ref "U5") (pin "12") (pinfunction "B7_12") (pintype "bidirectional"))
    )
    (net (code "100") (name "Net-(U5-B8)") (class "Default")
      (node (ref "R36") (pin "1") (pinfunction "1_1") (pintype "passive"))
      (node (ref "U5") (pin "11") (pinfunction "B8_11") (pintype "bidirectional"))
    )
    (net (code "101") (name "Net-(U6-B1)") (class "Default")
      (node (ref "R13") (pin "1") (pinfunction "1_1") (pintype "passive"))
      (node (ref "U6") (pin "18") (pinfunction "B1_18") (pintype "bidirectional"))
    )
    (net (code "102") (name "Net-(U6-B2)") (class "Default")
      (node (ref "R14") (pin "1") (pinfunction "1_1") (pintype "passive"))
      (node (ref "U6") (pin "17") (pinfunction "B2_17") (pintype "bidirectional"))
    )
    (net (code "103") (name "Net-(U6-B3)") (class "Default")
      (node (ref "R15") (pin "1") (pinfunction "1_1") (pintype "passive"))
      (node (ref "U6") (pin "16") (pinfunction "B3_16") (pintype "bidirectional"))
    )
    (net (code "104") (name "Net-(U6-B4)") (class "Default")
      (node (ref "R16") (pin "1") (pinfunction "1_1") (pintype "passive"))
      (node (ref "U6") (pin "15") (pinfunction "B4_15") (pintype "bidirectional"))
    )
    (net (code "105") (name "Net-(U6-B5)") (class "Default")
      (node (ref "R17") (pin "1") (pinfunction "1_1") (pintype "passive"))
      (node (ref "U6") (pin "14") (pinfunction "B5_14") (pintype "bidirectional"))
    )
    (net (code "106") (name "Net-(U6-B6)") (class "Default")
      (node (ref "R18") (pin "1") (pinfunction "1_1") (pintype "passive"))
      (node (ref "U6") (pin "13") (pinfunction "B6_13") (pintype "bidirectional"))
    )
    (net (code "107") (name "Net-(U6-B7)") (class "Default")
      (node (ref "R19") (pin "1") (pinfunction "1_1") (pintype "passive"))
      (node (ref "U6") (pin "12") (pinfunction "B7_12") (pintype "bidirectional"))
    )
    (net (code "108") (name "Net-(U6-B8)") (class "Default")
      (node (ref "R20") (pin "1") (pinfunction "1_1") (pintype "passive"))
      (node (ref "U6") (pin "11") (pinfunction "B8_11") (pintype "bidirectional"))
    )
    (net (code "109") (name "unconnected-(U2-NC-Pad73)") (class "Default")
      (node (ref "U2") (pin "73") (pinfunction "NC_73") (pintype "no_connect"))
    )
    (net (code "110") (name "unconnected-(U2-NC_2-Pad49)") (class "Default")
      (node (ref "U2") (pin "49") (pinfunction "NC_2_49") (pintype "no_connect"))
    )
    (net (code "111") (name "unconnected-(U2-PA0-WKUP-Pad23)") (class "Default")
      (node (ref "U2") (pin "23") (pinfunction "PA0-WKUP_23") (pintype "bidirectional"))
    )
    (net (code "112") (name "unconnected-(U2-PA3-Pad26)") (class "Default")
      (node (ref "U2") (pin "26") (pinfunction "PA3_26") (pintype "bidirectional"))
    )
    (net (code "113") (name "unconnected-(U2-PA4-Pad29)") (class "Default")
      (node (ref "U2") (pin "29") (pinfunction "PA4_29") (pintype "bidirectional"))
    )
    (net (code "114") (name "unconnected-(U2-PA5-Pad30)") (class "Default")
      (node (ref "U2") (pin "30") (pinfunction "PA5_30") (pintype "bidirectional"))
    )
    (net (code "115") (name "unconnected-(U2-PA8-Pad67)") (class "Default")
      (node (ref "U2") (pin "67") (pinfunction "PA8_67") (pintype "bidirectional"))
    )
    (net (code "116") (name "unconnected-(U2-PA13-Pad72)") (class "Default")
      (node (ref "U2") (pin "72") (pinfunction "PA13_72") (pintype "bidirectional"))
    )
    (net (code "117") (name "unconnected-(U2-PA14-Pad76)") (class "Default")
      (node (ref "U2") (pin "76") (pinfunction "PA14_76") (pintype "bidirectional"))
    )
    (net (code "118") (name "unconnected-(U2-PB1-Pad36)") (class "Default")
      (node (ref "U2") (pin "36") (pinfunction "PB1_36") (pintype "bidirectional"))
    )
    (net (code "119") (name "unconnected-(U2-PB6-Pad92)") (class "Default")
      (node (ref "U2") (pin "92") (pinfunction "PB6_92") (pintype "bidirectional"))
    )
    (net (code "120") (name "unconnected-(U2-PB7-Pad93)") (class "Default")
      (node (ref "U2") (pin "93") (pinfunction "PB7_93") (pintype "bidirectional"))
    )
    (net (code "121") (name "unconnected-(U2-PB10-Pad47)") (class "Default")
      (node (ref "U2") (pin "47") (pinfunction "PB10_47") (pintype "bidirectional"))
    )
    (net (code "122") (name "unconnected-(U2-PB14-Pad53)") (class "Default")
      (node (ref "U2") (pin "53") (pinfunction "PB14_53") (pintype "bidirectional"))
    )
    (net (code "123") (name "unconnected-(U2-PB15-Pad54)") (class "Default")
      (node (ref "U2") (pin "54") (pinfunction "PB15_54") (pintype "bidirectional"))
    )
    (net (code "124") (name "unconnected-(U2-PC0-Pad15)") (class "Default")
      (node (ref "U2") (pin "15") (pinfunction "PC0_15") (pintype "bidirectional"))
    )
    (net (code "125") (name "unconnected-(U2-PC2-Pad17)") (class "Default")
      (node (ref "U2") (pin "17") (pinfunction "PC2_17") (pintype "bidirectional"))
    )
    (net (code "126") (name "unconnected-(U2-PC3-Pad18)") (class "Default")
      (node (ref "U2") (pin "18") (pinfunction "PC3_18") (pintype "bidirectional"))
    )
    (net (code "127") (name "unconnected-(U2-PC6-Pad63)") (class "Default")
      (node (ref "U2") (pin "63") (pinfunction "PC6_63") (pintype "bidirectional"))
    )
    (net (code "128") (name "unconnected-(U2-PC10-Pad78)") (class "Default")
      (node (ref "U2") (pin "78") (pinfunction "PC10_78") (pintype "bidirectional"))
    )
    (net (code "129") (name "unconnected-(U2-PC11-Pad79)") (class "Default")
      (node (ref "U2") (pin "79") (pinfunction "PC11_79") (pintype "bidirectional"))
    )
    (net (code "130") (name "unconnected-(U2-PC12-Pad80)") (class "Default")
      (node (ref "U2") (pin "80") (pinfunction "PC12_80") (pintype "bidirectional"))
    )
    (net (code "131") (name "unconnected-(U2-PC14-OSC32_IN-Pad8)") (class "Default")
      (node (ref "U2") (pin "8") (pinfunction "PC14-OSC32_IN_8") (pintype "bidirectional"))
    )
    (net (code "132") (name "unconnected-(U2-PC15-OSC32_OUT-Pad9)") (class "Default")
      (node (ref "U2") (pin "9") (pinfunction "PC15-OSC32_OUT_9") (pintype "bidirectional"))
    )
    (net (code "133") (name "unconnected-(U2-PD1-Pad82)") (class "Default")
      (node (ref "U2") (pin "82") (pinfunction "PD1_82") (pintype "bidirectional"))
    )
    (net (code "134") (name "unconnected-(U2-PD2-Pad83)") (class "Default")
      (node (ref "U2") (pin "83") (pinfunction "PD2_83") (pintype "bidirectional"))
    )
    (net (code "135") (name "unconnected-(U2-PD3-Pad84)") (class "Default")
      (node (ref "U2") (pin "84") (pinfunction "PD3_84") (pintype "bidirectional"))
    )
    (net (code "136") (name "unconnected-(U2-PD4-Pad85)") (class "Default")
      (node (ref "U2") (pin "85") (pinfunction "PD4_85") (pintype "bidirectional"))
    )
    (net (code "137") (name "unconnected-(U2-PD5-Pad86)") (class "Default")
      (node (ref "U2") (pin "86") (pinfunction "PD5_86") (pintype "bidirectional"))
    )
    (net (code "138") (name "unconnected-(U2-PD6-Pad87)") (class "Default")
      (node (ref "U2") (pin "87") (pinfunction "PD6_87") (pintype "bidirectional"))
    )
    (net (code "139") (name "unconnected-(U2-PD7-Pad88)") (class "Default")
      (node (ref "U2") (pin "88") (pinfunction "PD7_88") (pintype "bidirectional"))
    )
    (net (code "140") (name "unconnected-(U2-PD8-Pad55)") (class "Default")
      (node (ref "U2") (pin "55") (pinfunction "PD8_55") (pintype "bidirectional"))
    )
    (net (code "141") (name "unconnected-(U2-PD9-Pad56)") (class "Default")
      (node (ref "U2") (pin "56") (pinfunction "PD9_56") (pintype "bidirectional"))
    )
    (net (code "142") (name "unconnected-(U2-PD10-Pad57)") (class "Default")
      (node (ref "U2") (pin "57") (pinfunction "PD10_57") (pintype "bidirectional"))
    )
    (net (code "143") (name "unconnected-(U2-PD11-Pad58)") (class "Default")
      (node (ref "U2") (pin "58") (pinfunction "PD11_58") (pintype "bidirectional"))
    )
    (net (code "144") (name "unconnected-(U2-PD12-Pad59)") (class "Default")
      (node (ref "U2") (pin "59") (pinfunction "PD12_59") (pintype "bidirectional"))
    )
    (net (code "145") (name "unconnected-(U2-PD13-Pad60)") (class "Default")
      (node (ref "U2") (pin "60") (pinfunction "PD13_60") (pintype "bidirectional"))
    )
    (net (code "146") (name "unconnected-(U2-PD14-Pad61)") (class "Default")
      (node (ref "U2") (pin "61") (pinfunction "PD14_61") (pintype "bidirectional"))
    )
    (net (code "147") (name "unconnected-(U2-PD15-Pad62)") (class "Default")
      (node (ref "U2") (pin "62") (pinfunction "PD15_62") (pintype "bidirectional"))
    )
  )
)
